# main.net
KiCad netlist of a schematic drawn in EAGLE
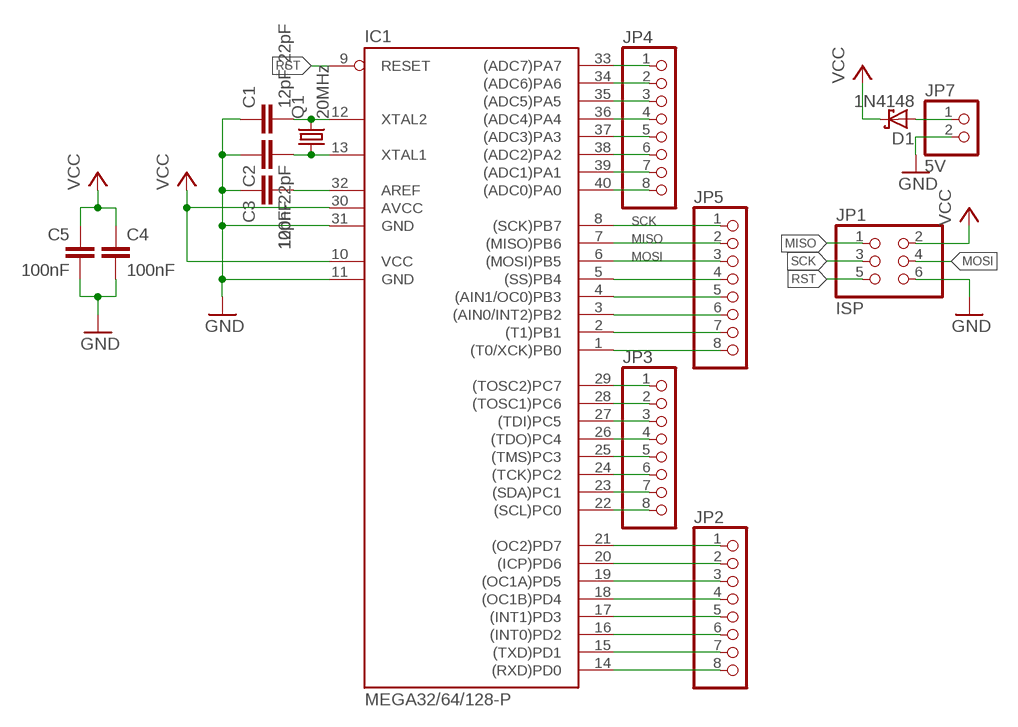
[diagram p0: schematic, sheet 1]

(export (version "E")
  (design (tool "Eeschema 10.0.6"))
  (components
    (comp (ref "C1")
      (value "12pF-22pF")
      (footprint "eagle-import:C0805K")
      (libsource (lib "eagle-import") (part "C-EUC0805K"))
    )
    (comp (ref "C2")
      (value "12pF-22pF")
      (footprint "eagle-import:C0805K")
      (libsource (lib "eagle-import") (part "C-EUC0805K"))
    )
    (comp (ref "C3")
      (value "100nF")
      (footprint "eagle-import:C0805K")
      (libsource (lib "eagle-import") (part "C-EUC0805K"))
    )
    (comp (ref "C4")
      (value "100nF")
      (footprint "eagle-import:C0805K")
      (libsource (lib "eagle-import") (part "C-EUC0805K"))
    )
    (comp (ref "C5")
      (value "100nF")
      (footprint "eagle-import:C0805K")
      (libsource (lib "eagle-import") (part "C-EUC0805K"))
    )
    (comp (ref "D1")
      (value "1N4148")
      (footprint "eagle-import:DO41-7.6")
      (libsource (lib "eagle-import") (part "1N5817-B"))
    )
    (comp (ref "IC1")
      (value "MEGA32/64/128-P")
      (footprint "eagle-import:DIL40")
      (fields (field (name "MPN") "ATMEGA32-16PU"))
      (libsource (lib "eagle-import") (part "MEGA32-P"))
    )
    (comp (ref "JP1")
      (value "ISP")
      (footprint "eagle-import:2X03")
      (libsource (lib "eagle-import") (part "PINHD-2X3"))
    )
    (comp (ref "JP2")
      (value "PINHD-1X8")
      (footprint "eagle-import:1X08")
      (libsource (lib "eagle-import") (part "PINHD-1X8"))
    )
    (comp (ref "JP3")
      (value "PINHD-1X8")
      (footprint "eagle-import:1X08")
      (libsource (lib "eagle-import") (part "PINHD-1X8"))
    )
    (comp (ref "JP4")
      (value "PINHD-1X8")
      (footprint "eagle-import:1X08")
      (libsource (lib "eagle-import") (part "PINHD-1X8"))
    )
    (comp (ref "JP5")
      (value "PINHD-1X8")
      (footprint "eagle-import:1X08")
      (libsource (lib "eagle-import") (part "PINHD-1X8"))
    )
    (comp (ref "JP7")
      (value "5V")
      (footprint "eagle-import:1X02")
      (libsource (lib "eagle-import") (part "PINHD-1X2"))
    )
    (comp (ref "Q1")
      (value "20MHz")
      (footprint "eagle-import:CSM-7X-DU")
      (libsource (lib "eagle-import") (part "CSM-7X-DU"))
    )
  )
  (nets
    (net (code "1") (name "GND") (class "Default")
      (node (ref "C1") (pin "1") (pinfunction "1_1") (pintype "passive"))
      (node (ref "C2") (pin "1") (pinfunction "1_1") (pintype "passive"))
      (node (ref "C3") (pin "1") (pinfunction "1_1") (pintype "passive"))
      (node (ref "C4") (pin "2") (pinfunction "2_2") (pintype "passive"))
      (node (ref "C5") (pin "2") (pinfunction "2_2") (pintype "passive"))
      (node (ref "IC1") (pin "11") (pinfunction "GND_11") (pintype "power_in"))
      (node (ref "IC1") (pin "31") (pinfunction "GND_31") (pintype "power_in"))
      (node (ref "JP1") (pin "6") (pinfunction "6_6") (pintype "passive"))
      (node (ref "JP7") (pin "2") (pinfunction "2_2") (pintype "passive"))
    )
    (net (code "2") (name "MISO") (class "Default")
      (node (ref "IC1") (pin "7") (pinfunction "(MISO)PB6_7") (pintype "bidirectional"))
      (node (ref "JP1") (pin "1") (pinfunction "1_1") (pintype "passive"))
      (node (ref "JP5") (pin "2") (pinfunction "2_2") (pintype "passive"))
    )
    (net (code "3") (name "MOSI") (class "Default")
      (node (ref "IC1") (pin "6") (pinfunction "(MOSI)PB5_6") (pintype "bidirectional"))
      (node (ref "JP1") (pin "4") (pinfunction "4_4") (pintype "passive"))
      (node (ref "JP5") (pin "3") (pinfunction "3_3") (pintype "passive"))
    )
    (net (code "4") (name "Net-(D1-PadA)") (class "Default")
      (node (ref "D1") (pin "A") (pinfunction "A_A") (pintype "passive"))
      (node (ref "JP7") (pin "1") (pinfunction "1_1") (pintype "passive"))
    )
    (net (code "5") (name "Net-(IC1-(ADC0)PA0)") (class "Default")
      (node (ref "IC1") (pin "40") (pinfunction "(ADC0)PA0_40") (pintype "bidirectional"))
      (node (ref "JP4") (pin "8") (pinfunction "8_8") (pintype "passive"))
    )
    (net (code "6") (name "Net-(IC1-(ADC1)PA1)") (class "Default")
      (node (ref "IC1") (pin "39") (pinfunction "(ADC1)PA1_39") (pintype "bidirectional"))
      (node (ref "JP4") (pin "7") (pinfunction "7_7") (pintype "passive"))
    )
    (net (code "7") (name "Net-(IC1-(ADC2)PA2)") (class "Default")
      (node (ref "IC1") (pin "38") (pinfunction "(ADC2)PA2_38") (pintype "bidirectional"))
      (node (ref "JP4") (pin "6") (pinfunction "6_6") (pintype "passive"))
    )
    (net (code "8") (name "Net-(IC1-(ADC3)PA3)") (class "Default")
      (node (ref "IC1") (pin "37") (pinfunction "(ADC3)PA3_37") (pintype "bidirectional"))
      (node (ref "JP4") (pin "5") (pinfunction "5_5") (pintype "passive"))
    )
    (net (code "9") (name "Net-(IC1-(ADC4)PA4)") (class "Default")
      (node (ref "IC1") (pin "36") (pinfunction "(ADC4)PA4_36") (pintype "bidirectional"))
      (node (ref "JP4") (pin "4") (pinfunction "4_4") (pintype "passive"))
    )
    (net (code "10") (name "Net-(IC1-(ADC5)PA5)") (class "Default")
      (node (ref "IC1") (pin "35") (pinfunction "(ADC5)PA5_35") (pintype "bidirectional"))
      (node (ref "JP4") (pin "3") (pinfunction "3_3") (pintype "passive"))
    )
    (net (code "11") (name "Net-(IC1-(ADC6)PA6)") (class "Default")
      (node (ref "IC1") (pin "34") (pinfunction "(ADC6)PA6_34") (pintype "bidirectional"))
      (node (ref "JP4") (pin "2") (pinfunction "2_2") (pintype "passive"))
    )
    (net (code "12") (name "Net-(IC1-(ADC7)PA7)") (class "Default")
      (node (ref "IC1") (pin "33") (pinfunction "(ADC7)PA7_33") (pintype "bidirectional"))
      (node (ref "JP4") (pin "1") (pinfunction "1_1") (pintype "passive"))
    )
    (net (code "13") (name "Net-(IC1-(AIN0{slash}INT2)PB2)") (class "Default")
      (node (ref "IC1") (pin "3") (pinfunction "(AIN0/INT2)PB2_3") (pintype "bidirectional"))
      (node (ref "JP5") (pin "6") (pinfunction "6_6") (pintype "passive"))
    )
    (net (code "14") (name "Net-(IC1-(AIN1{slash}OC0)PB3)") (class "Default")
      (node (ref "IC1") (pin "4") (pinfunction "(AIN1/OC0)PB3_4") (pintype "bidirectional"))
      (node (ref "JP5") (pin "5") (pinfunction "5_5") (pintype "passive"))
    )
    (net (code "15") (name "Net-(IC1-(ICP)PD6)") (class "Default")
      (node (ref "IC1") (pin "20") (pinfunction "(ICP)PD6_20") (pintype "bidirectional"))
      (node (ref "JP2") (pin "2") (pinfunction "2_2") (pintype "passive"))
    )
    (net (code "16") (name "Net-(IC1-(INT0)PD2)") (class "Default")
      (node (ref "IC1") (pin "16") (pinfunction "(INT0)PD2_16") (pintype "bidirectional"))
      (node (ref "JP2") (pin "6") (pinfunction "6_6") (pintype "passive"))
    )
    (net (code "17") (name "Net-(IC1-(INT1)PD3)") (class "Default")
      (node (ref "IC1") (pin "17") (pinfunction "(INT1)PD3_17") (pintype "bidirectional"))
      (node (ref "JP2") (pin "5") (pinfunction "5_5") (pintype "passive"))
    )
    (net (code "18") (name "Net-(IC1-(OC1A)PD5)") (class "Default")
      (node (ref "IC1") (pin "19") (pinfunction "(OC1A)PD5_19") (pintype "bidirectional"))
      (node (ref "JP2") (pin "3") (pinfunction "3_3") (pintype "passive"))
    )
    (net (code "19") (name "Net-(IC1-(OC1B)PD4)") (class "Default")
      (node (ref "IC1") (pin "18") (pinfunction "(OC1B)PD4_18") (pintype "bidirectional"))
      (node (ref "JP2") (pin "4") (pinfunction "4_4") (pintype "passive"))
    )
    (net (code "20") (name "Net-(IC1-(OC2)PD7)") (class "Default")
      (node (ref "IC1") (pin "21") (pinfunction "(OC2)PD7_21") (pintype "bidirectional"))
      (node (ref "JP2") (pin "1") (pinfunction "1_1") (pintype "passive"))
    )
    (net (code "21") (name "Net-(IC1-(RXD)PD0)") (class "Default")
      (node (ref "IC1") (pin "14") (pinfunction "(RXD)PD0_14") (pintype "bidirectional"))
      (node (ref "JP2") (pin "8") (pinfunction "8_8") (pintype "passive"))
    )
    (net (code "22") (name "Net-(IC1-(SCL)PC0)") (class "Default")
      (node (ref "IC1") (pin "22") (pinfunction "(SCL)PC0_22") (pintype "bidirectional"))
      (node (ref "JP3") (pin "8") (pinfunction "8_8") (pintype "passive"))
    )
    (net (code "23") (name "Net-(IC1-(SDA)PC1)") (class "Default")
      (node (ref "IC1") (pin "23") (pinfunction "(SDA)PC1_23") (pintype "bidirectional"))
      (node (ref "JP3") (pin "7") (pinfunction "7_7") (pintype "passive"))
    )
    (net (code "24") (name "Net-(IC1-(SS)PB4)") (class "Default")
      (node (ref "IC1") (pin "5") (pinfunction "(SS)PB4_5") (pintype "bidirectional"))
      (node (ref "JP5") (pin "4") (pinfunction "4_4") (pintype "passive"))
    )
    (net (code "25") (name "Net-(IC1-(T0{slash}XCK)PB0)") (class "Default")
      (node (ref "IC1") (pin "1") (pinfunction "(T0/XCK)PB0_1") (pintype "bidirectional"))
      (node (ref "JP5") (pin "8") (pinfunction "8_8") (pintype "passive"))
    )
    (net (code "26") (name "Net-(IC1-(T1)PB1)") (class "Default")
      (node (ref "IC1") (pin "2") (pinfunction "(T1)PB1_2") (pintype "bidirectional"))
      (node (ref "JP5") (pin "7") (pinfunction "7_7") (pintype "passive"))
    )
    (net (code "27") (name "Net-(IC1-(TCK)PC2)") (class "Default")
      (node (ref "IC1") (pin "24") (pinfunction "(TCK)PC2_24") (pintype "bidirectional"))
      (node (ref "JP3") (pin "6") (pinfunction "6_6") (pintype "passive"))
    )
    (net (code "28") (name "Net-(IC1-(TDI)PC5)") (class "Default")
      (node (ref "IC1") (pin "27") (pinfunction "(TDI)PC5_27") (pintype "bidirectional"))
      (node (ref "JP3") (pin "3") (pinfunction "3_3") (pintype "passive"))
    )
    (net (code "29") (name "Net-(IC1-(TDO)PC4)") (class "Default")
      (node (ref "IC1") (pin "26") (pinfunction "(TDO)PC4_26") (pintype "bidirectional"))
      (node (ref "JP3") (pin "4") (pinfunction "4_4") (pintype "passive"))
    )
    (net (code "30") (name "Net-(IC1-(TMS)PC3)") (class "Default")
      (node (ref "IC1") (pin "25") (pinfunction "(TMS)PC3_25") (pintype "bidirectional"))
      (node (ref "JP3") (pin "5") (pinfunction "5_5") (pintype "passive"))
    )
    (net (code "31") (name "Net-(IC1-(TOSC1)PC6)") (class "Default")
      (node (ref "IC1") (pin "28") (pinfunction "(TOSC1)PC6_28") (pintype "bidirectional"))
      (node (ref "JP3") (pin "2") (pinfunction "2_2") (pintype "passive"))
    )
    (net (code "32") (name "Net-(IC1-(TOSC2)PC7)") (class "Default")
      (node (ref "IC1") (pin "29") (pinfunction "(TOSC2)PC7_29") (pintype "bidirectional"))
      (node (ref "JP3") (pin "1") (pinfunction "1_1") (pintype "passive"))
    )
    (net (code "33") (name "Net-(IC1-(TXD)PD1)") (class "Default")
      (node (ref "IC1") (pin "15") (pinfunction "(TXD)PD1_15") (pintype "bidirectional"))
      (node (ref "JP2") (pin "7") (pinfunction "7_7") (pintype "passive"))
    )
    (net (code "34") (name "Net-(IC1-AREF)") (class "Default")
      (node (ref "C3") (pin "2") (pinfunction "2_2") (pintype "passive"))
      (node (ref "IC1") (pin "32") (pinfunction "AREF_32") (pintype "passive"))
    )
    (net (code "35") (name "Net-(IC1-XTAL1)") (class "Default")
      (node (ref "C2") (pin "2") (pinfunction "2_2") (pintype "passive"))
      (node (ref "IC1") (pin "13") (pinfunction "XTAL1_13") (pintype "bidirectional"))
      (node (ref "Q1") (pin "1") (pinfunction "1_1") (pintype "passive"))
    )
    (net (code "36") (name "Net-(IC1-XTAL2)") (class "Default")
      (node (ref "C1") (pin "2") (pinfunction "2_2") (pintype "passive"))
      (node (ref "IC1") (pin "12") (pinfunction "XTAL2_12") (pintype "bidirectional"))
      (node (ref "Q1") (pin "2") (pinfunction "2_2") (pintype "passive"))
    )
    (net (code "37") (name "RST") (class "Default")
      (node (ref "IC1") (pin "9") (pinfunction "RESET_9") (pintype "input"))
      (node (ref "JP1") (pin "5") (pinfunction "5_5") (pintype "passive"))
    )
    (net (code "38") (name "SCK") (class "Default")
      (node (ref "IC1") (pin "8") (pinfunction "(SCK)PB7_8") (pintype "bidirectional"))
      (node (ref "JP1") (pin "3") (pinfunction "3_3") (pintype "passive"))
      (node (ref "JP5") (pin "1") (pinfunction "1_1") (pintype "passive"))
    )
    (net (code "39") (name "VCC") (class "Default")
      (node (ref "C4") (pin "1") (pinfunction "1_1") (pintype "passive"))
      (node (ref "C5") (pin "1") (pinfunction "1_1") (pintype "passive"))
      (node (ref "D1") (pin "C") (pinfunction "C_C") (pintype "passive"))
      (node (ref "IC1") (pin "10") (pinfunction "VCC_10") (pintype "power_in"))
      (node (ref "IC1") (pin "30") (pinfunction "AVCC_30") (pintype "power_in"))
      (node (ref "JP1") (pin "2") (pinfunction "2_2") (pintype "passive"))
    )
  )
)
